# MasterRelayModule.net
KiCad netlist of a schematic drawn in Altium Designer
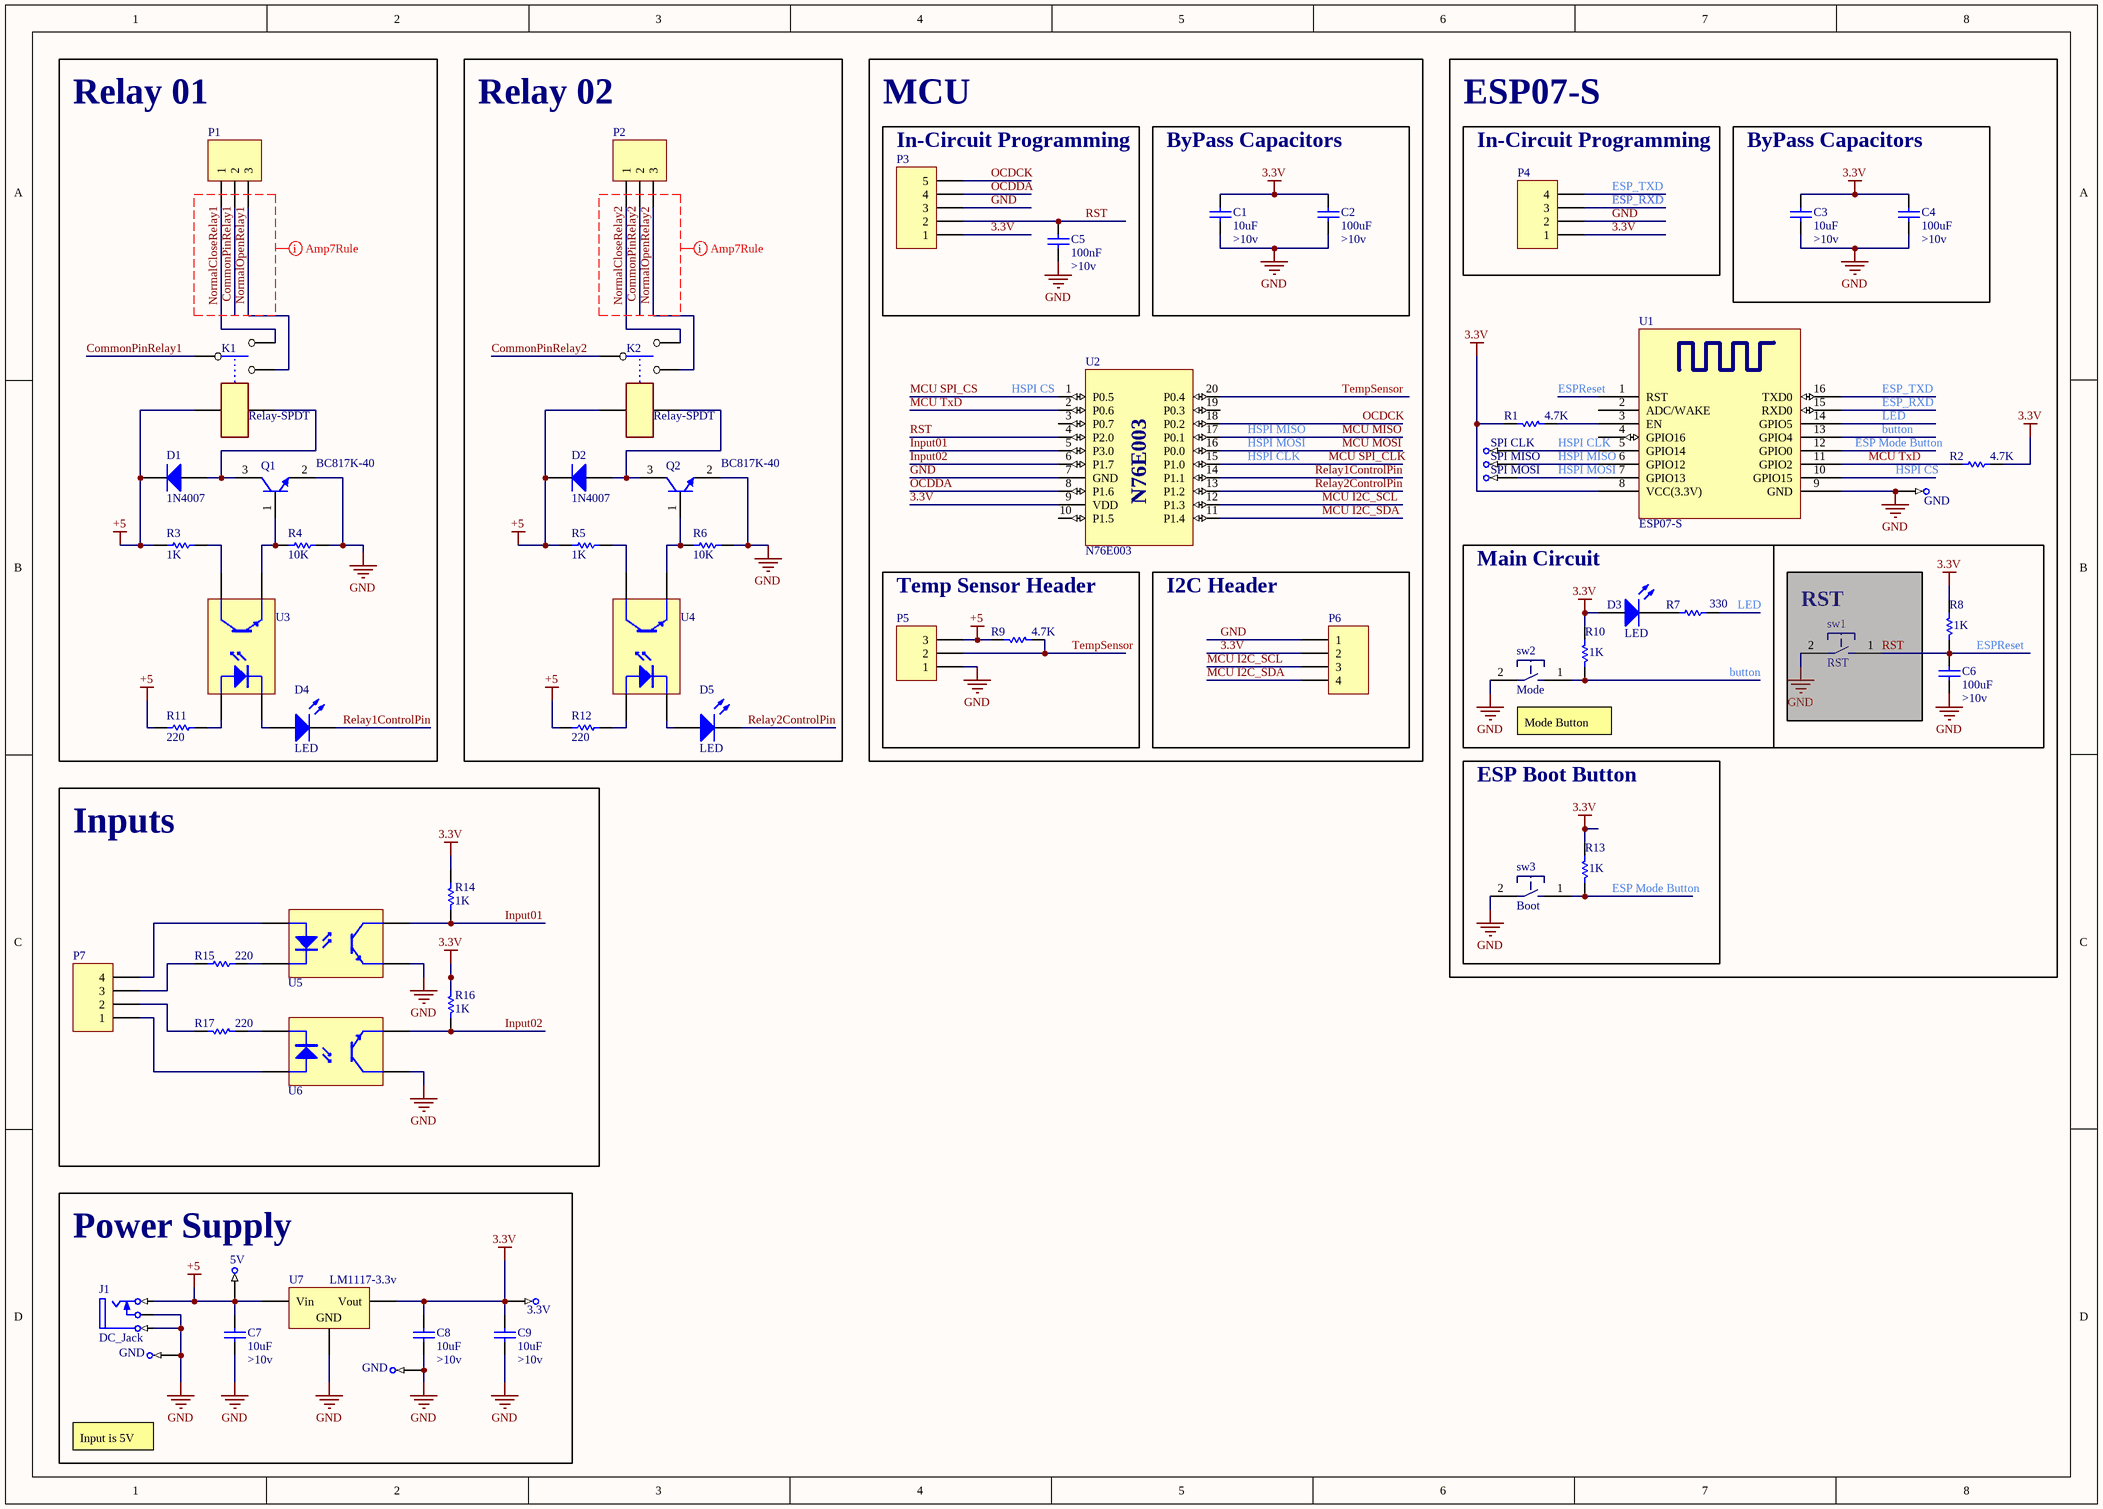
[diagram p0: MasterRelayModule.SchDoc]

(export (version "E")
  (design (tool "Eeschema 10.0.6"))
  (components
    (comp (ref "C1")
      (value "10uF")
      (footprint "MY_1210")
      (description "None polar capacitor")
      (fields (field (name "ASID PART NUMBER") "C-AS") (field (name "VOLTE") ">10v"))
      (libsource (lib "Mylib+Rev+4") (part "Cap ceramic"))
    )
    (comp (ref "C2")
      (value "100uF")
      (footprint "MY_1210")
      (description "None polar capacitor")
      (fields (field (name "ASID PART NUMBER") "C-AS") (field (name "VOLTE") ">10v"))
      (libsource (lib "Mylib+Rev+4") (part "Cap ceramic"))
    )
    (comp (ref "C3")
      (value "10uF")
      (footprint "MY_1210")
      (description "None polar capacitor")
      (fields (field (name "ASID PART NUMBER") "C-AS") (field (name "VOLTE") ">10v"))
      (libsource (lib "Mylib+Rev+4") (part "Cap ceramic"))
    )
    (comp (ref "C4")
      (value "100uF")
      (footprint "MY_1210")
      (description "None polar capacitor")
      (fields (field (name "ASID PART NUMBER") "C-AS") (field (name "VOLTE") ">10v"))
      (libsource (lib "Mylib+Rev+4") (part "Cap ceramic"))
    )
    (comp (ref "C5")
      (value "100nF")
      (footprint "MY_1210")
      (description "None polar capacitor")
      (fields (field (name "ASID PART NUMBER") "C-AS") (field (name "VOLTE") ">10v"))
      (libsource (lib "Mylib+Rev+4") (part "Cap ceramic"))
    )
    (comp (ref "C6")
      (value "100uF")
      (footprint "MY_1210")
      (description "None polar capacitor")
      (fields (field (name "ASID PART NUMBER") "C-AS") (field (name "VOLTE") ">10v"))
      (libsource (lib "Mylib+Rev+4") (part "Cap ceramic"))
    )
    (comp (ref "C7")
      (value "10uF")
      (footprint "MY_1210")
      (description "None polar capacitor")
      (fields (field (name "ASID PART NUMBER") "C-AS") (field (name "VOLTE") ">10v"))
      (libsource (lib "Mylib+Rev+4") (part "Cap ceramic"))
    )
    (comp (ref "C8")
      (value "10uF")
      (footprint "MY_1210")
      (description "None polar capacitor")
      (fields (field (name "ASID PART NUMBER") "C-AS") (field (name "VOLTE") ">10v"))
      (libsource (lib "Mylib+Rev+4") (part "Cap ceramic"))
    )
    (comp (ref "C9")
      (value "10uF")
      (footprint "MY_1210")
      (description "None polar capacitor")
      (fields (field (name "ASID PART NUMBER") "C-AS") (field (name "VOLTE") ">10v"))
      (libsource (lib "Mylib+Rev+4") (part "Cap ceramic"))
    )
    (comp (ref "D1")
      (value "1N4007")
      (footprint "MY_SMA")
      (description "1 Amp Diode")
      (fields (field (name "ASID PART NUMBER") "1n4007-AS"))
      (libsource (lib "Mylib+Rev+4") (part "1N4007"))
    )
    (comp (ref "D2")
      (value "1N4007")
      (footprint "MY_SMA")
      (description "1 Amp Diode")
      (fields (field (name "ASID PART NUMBER") "1n4007-AS"))
      (libsource (lib "Mylib+Rev+4") (part "1N4007"))
    )
    (comp (ref "D3")
      (value "LED")
      (footprint "MY_LED_0805")
      (description "Typical INFRARED GaAs LED")
      (fields (field (name "ASID PART NUMBER") "LED-AS"))
      (libsource (lib "Mylib+Rev+4") (part "LED"))
    )
    (comp (ref "D4")
      (value "LED")
      (footprint "MY_LED_0805")
      (description "Typical INFRARED GaAs LED")
      (fields (field (name "ASID PART NUMBER") "LED-AS"))
      (libsource (lib "Mylib+Rev+4") (part "LED"))
    )
    (comp (ref "D5")
      (value "LED")
      (footprint "MY_LED_0805")
      (description "Typical INFRARED GaAs LED")
      (fields (field (name "ASID PART NUMBER") "LED-AS"))
      (libsource (lib "Mylib+Rev+4") (part "LED"))
    )
    (comp (ref "J1")
      (value "DC_Jack")
      (footprint "My_DC_Jack")
      (fields (field (name "ASID PART NUMBER") "DC_Jack-AS"))
      (libsource (lib "Mylib+Rev+4") (part "DC_Jack"))
    )
    (comp (ref "K1")
      (value "Relay-SPDT")
      (footprint "My_rel")
      (description "Standard single contact relay")
      (fields (field (name "ASID PART NUMBER") "Relay-SPDT-AS"))
      (libsource (lib "Mylib+Rev+4") (part "Relay-SPDT"))
    )
    (comp (ref "K2")
      (value "Relay-SPDT")
      (footprint "My_rel")
      (description "Standard single contact relay")
      (fields (field (name "ASID PART NUMBER") "Relay-SPDT-AS"))
      (libsource (lib "Mylib+Rev+4") (part "Relay-SPDT"))
    )
    (comp (ref "P1")
      (value "Header 3")
      (footprint "MY_MSTBA3")
      (description "Header, 3-Pin")
      (fields (field (name "ASID PART NUMBER") "Header 3-AS"))
      (libsource (lib "") (part "Header 3_1"))
    )
    (comp (ref "P2")
      (value "Header 3")
      (footprint "MY_MSTBA3")
      (description "Header, 3-Pin")
      (fields (field (name "ASID PART NUMBER") "Header 3-AS"))
      (libsource (lib "") (part "Header 3_1"))
    )
    (comp (ref "P3")
      (value "Header 5")
      (footprint "My_1X05")
      (description "Header, 5-Pin")
      (fields (field (name "ASID PART NUMBER") "Header 5-AS"))
      (libsource (lib "Mylib+Rev+4") (part "Header 5"))
    )
    (comp (ref "P4")
      (value "Header 4")
      (footprint "My_1X04")
      (description "Header, 4-Pin")
      (fields (field (name "ASID PART NUMBER") "Header 4-AS"))
      (libsource (lib "") (part "Header 4_1"))
    )
    (comp (ref "P5")
      (value "Header 3")
      (footprint "My_1X03")
      (description "Header, 3-Pin")
      (fields (field (name "ASID PART NUMBER") "Header 3-AS"))
      (libsource (lib "Mylib+Rev+4") (part "Header 3"))
    )
    (comp (ref "P6")
      (value "Header 4")
      (footprint "MY_FE04W")
      (description "Header, 4-Pin")
      (fields (field (name "ASID PART NUMBER") "Header 4-AS"))
      (libsource (lib "Mylib+Rev+4") (part "Header 4"))
    )
    (comp (ref "P7")
      (value "Header 4")
      (footprint "MY_MSTBA4")
      (description "Header, 4-Pin")
      (fields (field (name "ASID PART NUMBER") "Header 4-AS"))
      (libsource (lib "") (part "Header 4_1"))
    )
    (comp (ref "Q1")
      (value "BC817K-40")
      (footprint "INF-SOT23_N")
      (description "NPN Silicon AF Transistor, 45 V VCEO, 500 mA IC, SOT23, Reel, Green")
      (fields (field (name "MANUFACTURER") "Infineon"))
      (libsource (lib "Infineon_Transistor_&_Diode") (part "BC817K-40"))
    )
    (comp (ref "Q2")
      (value "BC817K-40")
      (footprint "INF-SOT23_N")
      (description "NPN Silicon AF Transistor, 45 V VCEO, 500 mA IC, SOT23, Reel, Green")
      (fields (field (name "MANUFACTURER") "Infineon"))
      (libsource (lib "Infineon_Transistor_&_Diode") (part "BC817K-40"))
    )
    (comp (ref "R1")
      (value "4.7K")
      (footprint "MY_0805")
      (description "Standard resistor")
      (fields (field (name "ASID PART NUMBER") "Res-AS"))
      (libsource (lib "Mylib+Rev+4") (part "Res"))
    )
    (comp (ref "R2")
      (value "4.7K")
      (footprint "MY_0805")
      (description "Standard resistor")
      (fields (field (name "ASID PART NUMBER") "Res-AS"))
      (libsource (lib "Mylib+Rev+4") (part "Res"))
    )
    (comp (ref "R3")
      (value "1K")
      (footprint "MY_0805")
      (description "Standard resistor")
      (fields (field (name "ASID PART NUMBER") "Res-AS"))
      (libsource (lib "Mylib+Rev+4") (part "Res"))
    )
    (comp (ref "R4")
      (value "10K")
      (footprint "MY_0805")
      (description "Standard resistor")
      (fields (field (name "ASID PART NUMBER") "Res-AS"))
      (libsource (lib "Mylib+Rev+4") (part "Res"))
    )
    (comp (ref "R5")
      (value "1K")
      (footprint "MY_0805")
      (description "Standard resistor")
      (fields (field (name "ASID PART NUMBER") "Res-AS"))
      (libsource (lib "Mylib+Rev+4") (part "Res"))
    )
    (comp (ref "R6")
      (value "10K")
      (footprint "MY_0805")
      (description "Standard resistor")
      (fields (field (name "ASID PART NUMBER") "Res-AS"))
      (libsource (lib "Mylib+Rev+4") (part "Res"))
    )
    (comp (ref "R7")
      (value "330")
      (footprint "MY_0805")
      (description "Standard resistor")
      (fields (field (name "ASID PART NUMBER") "Res-AS"))
      (libsource (lib "Mylib+Rev+4") (part "Res"))
    )
    (comp (ref "R8")
      (value "1K")
      (footprint "MY_0805")
      (description "Standard resistor")
      (fields (field (name "ASID PART NUMBER") "Res-AS"))
      (libsource (lib "Mylib+Rev+4") (part "Res"))
    )
    (comp (ref "R9")
      (value "4.7K")
      (footprint "MY_0805")
      (description "Standard resistor")
      (fields (field (name "ASID PART NUMBER") "Res-AS"))
      (libsource (lib "Mylib+Rev+4") (part "Res"))
    )
    (comp (ref "R10")
      (value "1K")
      (footprint "MY_0805")
      (description "Standard resistor")
      (fields (field (name "ASID PART NUMBER") "Res-AS"))
      (libsource (lib "Mylib+Rev+4") (part "Res"))
    )
    (comp (ref "R11")
      (value "220")
      (footprint "MY_0805")
      (description "Standard resistor")
      (fields (field (name "ASID PART NUMBER") "Res-AS"))
      (libsource (lib "Mylib+Rev+4") (part "Res"))
    )
    (comp (ref "R12")
      (value "220")
      (footprint "MY_0805")
      (description "Standard resistor")
      (fields (field (name "ASID PART NUMBER") "Res-AS"))
      (libsource (lib "Mylib+Rev+4") (part "Res"))
    )
    (comp (ref "R13")
      (value "1K")
      (footprint "MY_0805")
      (description "Standard resistor")
      (fields (field (name "ASID PART NUMBER") "Res-AS"))
      (libsource (lib "Mylib+Rev+4") (part "Res"))
    )
    (comp (ref "R14")
      (value "1K")
      (footprint "MY_0805")
      (description "Standard resistor")
      (fields (field (name "ASID PART NUMBER") "Res-AS"))
      (libsource (lib "Mylib+Rev+4") (part "Res"))
    )
    (comp (ref "R15")
      (value "220")
      (footprint "MY_0805")
      (description "Standard resistor")
      (fields (field (name "ASID PART NUMBER") "Res-AS"))
      (libsource (lib "Mylib+Rev+4") (part "Res"))
    )
    (comp (ref "R16")
      (value "1K")
      (footprint "MY_0805")
      (description "Standard resistor")
      (fields (field (name "ASID PART NUMBER") "Res-AS"))
      (libsource (lib "Mylib+Rev+4") (part "Res"))
    )
    (comp (ref "R17")
      (value "220")
      (footprint "MY_0805")
      (description "Standard resistor")
      (fields (field (name "ASID PART NUMBER") "Res-AS"))
      (libsource (lib "Mylib+Rev+4") (part "Res"))
    )
    (comp (ref "sw1")
      (value "RST")
      (footprint "MY_TACTILE-SMD")
      (description "small tac switch")
      (fields (field (name "ASID PART NUMBER") "Tac switch-AS"))
      (libsource (lib "Mylib+Rev+4") (part "Tac switch"))
    )
    (comp (ref "sw2")
      (value "Mode")
      (footprint "MY_TACTILE-SMD")
      (description "small tac switch")
      (fields (field (name "ASID PART NUMBER") "Tac switch-AS"))
      (libsource (lib "Mylib+Rev+4") (part "Tac switch"))
    )
    (comp (ref "sw3")
      (value "Boot")
      (footprint "MY_TACTILE-SMD")
      (description "small tac switch")
      (fields (field (name "ASID PART NUMBER") "Tac switch-AS"))
      (libsource (lib "Mylib+Rev+4") (part "Tac switch"))
    )
    (comp (ref "TP1")
      (value "SPI CLK")
      (footprint "MY_Testpad1")
      (description "Test point")
      (fields (field (name "ASID PART NUMBER") "Test Point-AS"))
      (libsource (lib "Mylib+Rev+4") (part "Test Point"))
    )
    (comp (ref "TP2")
      (value "SPI MISO")
      (footprint "MY_Testpad1")
      (description "Test point")
      (fields (field (name "ASID PART NUMBER") "Test Point-AS"))
      (libsource (lib "Mylib+Rev+4") (part "Test Point"))
    )
    (comp (ref "TP3")
      (value "SPI MOSI")
      (footprint "MY_Testpad1")
      (description "Test point")
      (fields (field (name "ASID PART NUMBER") "Test Point-AS"))
      (libsource (lib "Mylib+Rev+4") (part "Test Point"))
    )
    (comp (ref "TP4")
      (value "5V")
      (footprint "MY_Testpad1")
      (description "Test point")
      (fields (field (name "ASID PART NUMBER") "Test Point-AS"))
      (libsource (lib "Mylib+Rev+4") (part "Test Point"))
    )
    (comp (ref "TP5")
      (value "3.3V")
      (footprint "MY_Testpad1")
      (description "Test point")
      (fields (field (name "ASID PART NUMBER") "Test Point-AS"))
      (libsource (lib "Mylib+Rev+4") (part "Test Point"))
    )
    (comp (ref "TP6")
      (value "GND")
      (footprint "MY_Testpad1")
      (description "Test point")
      (fields (field (name "ASID PART NUMBER") "Test Point-AS"))
      (libsource (lib "Mylib+Rev+4") (part "Test Point"))
    )
    (comp (ref "TP7")
      (value "GND")
      (footprint "MY_Testpad1")
      (description "Test point")
      (fields (field (name "ASID PART NUMBER") "Test Point-AS"))
      (libsource (lib "Mylib+Rev+4") (part "Test Point"))
    )
    (comp (ref "TP8")
      (value "GND")
      (footprint "MY_Testpad1")
      (description "Test point")
      (fields (field (name "ASID PART NUMBER") "Test Point-AS"))
      (libsource (lib "Mylib+Rev+4") (part "Test Point"))
    )
    (comp (ref "U1") (value "ESP07-S") (footprint "ESP07-S") (libsource (lib "myLib") (part "ESP07-S")))
    (comp (ref "U2") (value "N76E003") (footprint "SOP_20") (libsource (lib "myLib") (part "N76E003")))
    (comp (ref "U3")
      (value "Optoisolator")
      (footprint "MY_OPTO_SMD4-7")
      (fields (field (name "ASID PART NUMBER") "Optoisolator-AS"))
      (libsource (lib "Mylib+Rev+4") (part "Optoisolator"))
    )
    (comp (ref "U4")
      (value "Optoisolator")
      (footprint "MY_OPTO_SMD4-7")
      (fields (field (name "ASID PART NUMBER") "Optoisolator-AS"))
      (libsource (lib "Mylib+Rev+4") (part "Optoisolator"))
    )
    (comp (ref "U5")
      (value "Optoisolator")
      (footprint "MY_OPTO_SMD4-7")
      (fields (field (name "ASID PART NUMBER") "Optoisolator-AS"))
      (libsource (lib "") (part "Optoisolator_1"))
    )
    (comp (ref "U6")
      (value "Optoisolator")
      (footprint "MY_OPTO_SMD4-7")
      (fields (field (name "ASID PART NUMBER") "Optoisolator-AS"))
      (libsource (lib "Mylib+Rev+4") (part "Optoisolator"))
    )
    (comp (ref "U7")
      (value "LM1117-3.3v")
      (footprint "MY_SOT223")
      (description "Low Drop Voltage Reg")
      (fields (field (name "ASID PART NUMBER") "LM1117-AS"))
      (libsource (lib "Mylib+Rev+4") (part "LM1117"))
    )
  )
  (nets
    (net (code "1") (name "+5") (class "Default")
      (node (ref "C7") (pin "2") (pinfunction "2_2") (pintype "passive"))
      (node (ref "D1") (pin "K") (pinfunction "K_K") (pintype "passive"))
      (node (ref "D2") (pin "K") (pinfunction "K_K") (pintype "passive"))
      (node (ref "J1") (pin "1") (pinfunction "T_1") (pintype "input"))
      (node (ref "K1") (pin "4") (pinfunction "4_4") (pintype "passive"))
      (node (ref "K2") (pin "4") (pinfunction "4_4") (pintype "passive"))
      (node (ref "P5") (pin "3") (pinfunction "3_3") (pintype "passive"))
      (node (ref "R11") (pin "2") (pinfunction "2_2") (pintype "passive"))
      (node (ref "R12") (pin "2") (pinfunction "2_2") (pintype "passive"))
      (node (ref "R3") (pin "2") (pinfunction "2_2") (pintype "passive"))
      (node (ref "R5") (pin "2") (pinfunction "2_2") (pintype "passive"))
      (node (ref "R9") (pin "1") (pinfunction "1_1") (pintype "passive"))
      (node (ref "TP4") (pin "1") (pinfunction "1_1") (pintype "input"))
      (node (ref "U7") (pin "3") (pinfunction "Vin_3") (pintype "passive"))
    )
    (net (code "2") (name "/CommonPinRelay1") (class "Default")
      (node (ref "K1") (pin "1") (pinfunction "1_1") (pintype "passive"))
      (node (ref "P1") (pin "2") (pinfunction "2_2") (pintype "passive"))
    )
    (net (code "3") (name "/CommonPinRelay2") (class "Default")
      (node (ref "K2") (pin "1") (pinfunction "1_1") (pintype "passive"))
      (node (ref "P2") (pin "2") (pinfunction "2_2") (pintype "passive"))
    )
    (net (code "4") (name "/ESP Mode Button") (class "Default")
      (node (ref "R13") (pin "2") (pinfunction "2_2") (pintype "passive"))
      (node (ref "U1") (pin "12") (pinfunction "GPIO0_12") (pintype "passive"))
      (node (ref "sw3") (pin "1") (pinfunction "1_1") (pintype "passive"))
    )
    (net (code "5") (name "/ESPReset") (class "Default")
      (node (ref "C5") (pin "2") (pinfunction "2_2") (pintype "passive"))
      (node (ref "C6") (pin "2") (pinfunction "2_2") (pintype "passive"))
      (node (ref "P3") (pin "2") (pinfunction "2_2") (pintype "passive"))
      (node (ref "R8") (pin "2") (pinfunction "2_2") (pintype "passive"))
      (node (ref "U1") (pin "1") (pinfunction "RST_1") (pintype "passive"))
      (node (ref "U2") (pin "4") (pinfunction "P2.0_4") (pintype "bidirectional"))
      (node (ref "sw1") (pin "1") (pinfunction "1_1") (pintype "passive"))
    )
    (net (code "6") (name "/ESP_RXD") (class "Default")
      (node (ref "P4") (pin "3") (pinfunction "3_3") (pintype "passive"))
      (node (ref "U1") (pin "15") (pinfunction "RXD0_15") (pintype "bidirectional"))
    )
    (net (code "7") (name "/ESP_TXD") (class "Default")
      (node (ref "P4") (pin "4") (pinfunction "4_4") (pintype "passive"))
      (node (ref "U1") (pin "16") (pinfunction "TXD0_16") (pintype "bidirectional"))
    )
    (net (code "8") (name "/HSPI CLK") (class "Default")
      (node (ref "TP1") (pin "1") (pinfunction "1_1") (pintype "input"))
      (node (ref "U1") (pin "5") (pinfunction "GPIO14_5") (pintype "passive"))
      (node (ref "U2") (pin "15") (pinfunction "P1.0_15") (pintype "bidirectional"))
    )
    (net (code "9") (name "/HSPI CS") (class "Default")
      (node (ref "U1") (pin "10") (pinfunction "GPIO15_10") (pintype "passive"))
      (node (ref "U2") (pin "1") (pinfunction "P0.5_1") (pintype "bidirectional"))
    )
    (net (code "10") (name "/HSPI MISO") (class "Default")
      (node (ref "TP2") (pin "1") (pinfunction "1_1") (pintype "input"))
      (node (ref "U1") (pin "6") (pinfunction "GPIO12_6") (pintype "passive"))
      (node (ref "U2") (pin "17") (pinfunction "P0.1_17") (pintype "bidirectional"))
    )
    (net (code "11") (name "/HSPI MOSI") (class "Default")
      (node (ref "TP3") (pin "1") (pinfunction "1_1") (pintype "input"))
      (node (ref "U1") (pin "7") (pinfunction "GPIO13_7") (pintype "passive"))
      (node (ref "U2") (pin "16") (pinfunction "P0.0_16") (pintype "bidirectional"))
    )
    (net (code "12") (name "/Input01") (class "Default")
      (node (ref "R14") (pin "2") (pinfunction "2_2") (pintype "passive"))
      (node (ref "U2") (pin "5") (pinfunction "P3.0_5") (pintype "bidirectional"))
      (node (ref "U5") (pin "4") (pinfunction "C_4") (pintype "passive"))
    )
    (net (code "13") (name "/Input02") (class "Default")
      (node (ref "R16") (pin "2") (pinfunction "2_2") (pintype "passive"))
      (node (ref "U2") (pin "6") (pinfunction "P1.7_6") (pintype "bidirectional"))
      (node (ref "U6") (pin "3") (pinfunction "E_3") (pintype "passive"))
    )
    (net (code "14") (name "/LED") (class "Default")
      (node (ref "R7") (pin "2") (pinfunction "2_2") (pintype "passive"))
      (node (ref "U1") (pin "14") (pinfunction "GPIO5_14") (pintype "passive"))
    )
    (net (code "15") (name "/MCU I2C_SCL") (class "Default")
      (node (ref "P6") (pin "3") (pinfunction "3_3") (pintype "passive"))
      (node (ref "U2") (pin "12") (pinfunction "P1.3_12") (pintype "bidirectional"))
    )
    (net (code "16") (name "/MCU I2C_SDA") (class "Default")
      (node (ref "P6") (pin "4") (pinfunction "4_4") (pintype "passive"))
      (node (ref "U2") (pin "11") (pinfunction "P1.4_11") (pintype "bidirectional"))
    )
    (net (code "17") (name "/MCU TxD") (class "Default")
      (node (ref "R2") (pin "2") (pinfunction "2_2") (pintype "passive"))
      (node (ref "U1") (pin "11") (pinfunction "GPIO2_11") (pintype "passive"))
      (node (ref "U2") (pin "2") (pinfunction "P0.6_2") (pintype "bidirectional"))
    )
    (net (code "18") (name "/NormalCloseRelay1") (class "Default")
      (node (ref "K1") (pin "2") (pinfunction "2_2") (pintype "passive"))
      (node (ref "P1") (pin "1") (pinfunction "1_1") (pintype "passive"))
    )
    (net (code "19") (name "/NormalCloseRelay2") (class "Default")
      (node (ref "K2") (pin "2") (pinfunction "2_2") (pintype "passive"))
      (node (ref "P2") (pin "1") (pinfunction "1_1") (pintype "passive"))
    )
    (net (code "20") (name "/NormalOpenRelay1") (class "Default")
      (node (ref "K1") (pin "3") (pinfunction "3_3") (pintype "passive"))
      (node (ref "P1") (pin "3") (pinfunction "3_3") (pintype "passive"))
    )
    (net (code "21") (name "/NormalOpenRelay2") (class "Default")
      (node (ref "K2") (pin "3") (pinfunction "3_3") (pintype "passive"))
      (node (ref "P2") (pin "3") (pinfunction "3_3") (pintype "passive"))
    )
    (net (code "22") (name "/OCDCK") (class "Default")
      (node (ref "P3") (pin "5") (pinfunction "5_5") (pintype "passive"))
      (node (ref "U2") (pin "18") (pinfunction "P0.2_18") (pintype "bidirectional"))
    )
    (net (code "23") (name "/OCDDA") (class "Default")
      (node (ref "P3") (pin "4") (pinfunction "4_4") (pintype "passive"))
      (node (ref "U2") (pin "8") (pinfunction "P1.6_8") (pintype "bidirectional"))
    )
    (net (code "24") (name "/Relay1ControlPin") (class "Default")
      (node (ref "D4") (pin "K") (pinfunction "K_K") (pintype "passive"))
      (node (ref "U2") (pin "14") (pinfunction "P1.1_14") (pintype "bidirectional"))
    )
    (net (code "25") (name "/Relay2ControlPin") (class "Default")
      (node (ref "D5") (pin "K") (pinfunction "K_K") (pintype "passive"))
      (node (ref "U2") (pin "13") (pinfunction "P1.2_13") (pintype "bidirectional"))
    )
    (net (code "26") (name "/TempSensor") (class "Default")
      (node (ref "P5") (pin "2") (pinfunction "2_2") (pintype "passive"))
      (node (ref "R9") (pin "2") (pinfunction "2_2") (pintype "passive"))
      (node (ref "U2") (pin "20") (pinfunction "P0.4_20") (pintype "bidirectional"))
    )
    (net (code "27") (name "/button") (class "Default")
      (node (ref "R10") (pin "2") (pinfunction "2_2") (pintype "passive"))
      (node (ref "U1") (pin "13") (pinfunction "GPIO4_13") (pintype "passive"))
      (node (ref "sw2") (pin "1") (pinfunction "1_1") (pintype "passive"))
    )
    (net (code "28") (name "3.3V") (class "Default")
      (node (ref "C1") (pin "2") (pinfunction "2_2") (pintype "passive"))
      (node (ref "C2") (pin "2") (pinfunction "2_2") (pintype "passive"))
      (node (ref "C3") (pin "2") (pinfunction "2_2") (pintype "passive"))
      (node (ref "C4") (pin "2") (pinfunction "2_2") (pintype "passive"))
      (node (ref "C8") (pin "2") (pinfunction "2_2") (pintype "passive"))
      (node (ref "C9") (pin "2") (pinfunction "2_2") (pintype "passive"))
      (node (ref "D3") (pin "A") (pinfunction "A_A") (pintype "passive"))
      (node (ref "P3") (pin "1") (pinfunction "1_1") (pintype "passive"))
      (node (ref "P4") (pin "1") (pinfunction "1_1") (pintype "passive"))
      (node (ref "P6") (pin "2") (pinfunction "2_2") (pintype "passive"))
      (node (ref "R1") (pin "1") (pinfunction "1_1") (pintype "passive"))
      (node (ref "R10") (pin "1") (pinfunction "1_1") (pintype "passive"))
      (node (ref "R13") (pin "1") (pinfunction "1_1") (pintype "passive"))
      (node (ref "R14") (pin "1") (pinfunction "1_1") (pintype "passive"))
      (node (ref "R16") (pin "1") (pinfunction "1_1") (pintype "passive"))
      (node (ref "R2") (pin "1") (pinfunction "1_1") (pintype "passive"))
      (node (ref "R8") (pin "1") (pinfunction "1_1") (pintype "passive"))
      (node (ref "TP5") (pin "1") (pinfunction "1_1") (pintype "input"))
      (node (ref "U1") (pin "8") (pinfunction "VCC(3.3V)_8") (pintype "passive"))
      (node (ref "U2") (pin "9") (pinfunction "VDD_9") (pintype "power_in"))
      (node (ref "U7") (pin "2") (pinfunction "Vout_2") (pintype "passive"))
    )
    (net (code "29") (name "GND") (class "Default")
      (node (ref "C1") (pin "1") (pinfunction "1_1") (pintype "passive"))
      (node (ref "C2") (pin "1") (pinfunction "1_1") (pintype "passive"))
      (node (ref "C3") (pin "1") (pinfunction "1_1") (pintype "passive"))
      (node (ref "C4") (pin "1") (pinfunction "1_1") (pintype "passive"))
      (node (ref "C5") (pin "1") (pinfunction "1_1") (pintype "passive"))
      (node (ref "C6") (pin "1") (pinfunction "1_1") (pintype "passive"))
      (node (ref "C7") (pin "1") (pinfunction "1_1") (pintype "passive"))
      (node (ref "C8") (pin "1") (pinfunction "1_1") (pintype "passive"))
      (node (ref "C9") (pin "1") (pinfunction "1_1") (pintype "passive"))
      (node (ref "J1") (pin "2") (pinfunction "TN_2") (pintype "passive"))
      (node (ref "J1") (pin "3") (pinfunction "S_3") (pintype "input"))
      (node (ref "P3") (pin "3") (pinfunction "3_3") (pintype "passive"))
      (node (ref "P4") (pin "2") (pinfunction "2_2") (pintype "passive"))
      (node (ref "P5") (pin "1") (pinfunction "1_1") (pintype "passive"))
      (node (ref "P6") (pin "1") (pinfunction "1_1") (pintype "passive"))
      (node (ref "Q1") (pin "2") (pinfunction "E_2") (pintype "passive"))
      (node (ref "Q2") (pin "2") (pinfunction "E_2") (pintype "passive"))
      (node (ref "R4") (pin "1") (pinfunction "1_1") (pintype "passive"))
      (node (ref "R6") (pin "1") (pinfunction "1_1") (pintype "passive"))
      (node (ref "TP6") (pin "1") (pinfunction "1_1") (pintype "input"))
      (node (ref "TP7") (pin "1") (pinfunction "1_1") (pintype "input"))
      (node (ref "TP8") (pin "1") (pinfunction "1_1") (pintype "input"))
      (node (ref "U1") (pin "9") (pinfunction "GND_9") (pintype "passive"))
      (node (ref "U2") (pin "7") (pinfunction "GND_7") (pintype "power_in"))
      (node (ref "U5") (pin "3") (pinfunction "E_3") (pintype "passive"))
      (node (ref "U6") (pin "4") (pinfunction "C_4") (pintype "passive"))
      (node (ref "U7") (pin "1") (pinfunction "GND_1") (pintype "passive"))
      (node (ref "sw1") (pin "2") (pinfunction "2_2") (pintype "passive"))
      (node (ref "sw2") (pin "2") (pinfunction "2_2") (pintype "passive"))
      (node (ref "sw3") (pin "2") (pinfunction "2_2") (pintype "passive"))
    )
    (net (code "30") (name "Net-(D3-PadK)") (class "Default")
      (node (ref "D3") (pin "K") (pinfunction "K_K") (pintype "passive"))
      (node (ref "R7") (pin "1") (pinfunction "1_1") (pintype "passive"))
    )
    (net (code "31") (name "Net-(P7-Pad2)") (class "Default")
      (node (ref "P7") (pin "2") (pinfunction "2_2") (pintype "passive"))
      (node (ref "R17") (pin "2") (pinfunction "2_2") (pintype "passive"))
    )
    (net (code "32") (name "Net-(P7-Pad3)") (class "Default")
      (node (ref "P7") (pin "3") (pinfunction "3_3") (pintype "passive"))
      (node (ref "R15") (pin "2") (pinfunction "2_2") (pintype "passive"))
    )
    (net (code "33") (name "Net-(Q1-B)") (class "Default")
      (node (ref "Q1") (pin "1") (pinfunction "B_1") (pintype "passive"))
      (node (ref "R4") (pin "2") (pinfunction "2_2") (pintype "passive"))
      (node (ref "U3") (pin "3") (pinfunction "E_3") (pintype "passive"))
    )
    (net (code "34") (name "Net-(Q1-C)") (class "Default")
      (node (ref "D1") (pin "A") (pinfunction "A_A") (pintype "passive"))
      (node (ref "K1") (pin "5") (pinfunction "5_5") (pintype "passive"))
      (node (ref "Q1") (pin "3") (pinfunction "C_3") (pintype "passive"))
    )
    (net (code "35") (name "Net-(Q2-B)") (class "Default")
      (node (ref "Q2") (pin "1") (pinfunction "B_1") (pintype "passive"))
      (node (ref "R6") (pin "2") (pinfunction "2_2") (pintype "passive"))
      (node (ref "U4") (pin "3") (pinfunction "E_3") (pintype "passive"))
    )
    (net (code "36") (name "Net-(Q2-C)") (class "Default")
      (node (ref "D2") (pin "A") (pinfunction "A_A") (pintype "passive"))
      (node (ref "K2") (pin "5") (pinfunction "5_5") (pintype "passive"))
      (node (ref "Q2") (pin "3") (pinfunction "C_3") (pintype "passive"))
    )
    (net (code "37") (name "Net-(U1-EN)") (class "Default")
      (node (ref "R1") (pin "2") (pinfunction "2_2") (pintype "passive"))
      (node (ref "U1") (pin "3") (pinfunction "EN_3") (pintype "passive"))
    )
    (net (code "38") (name "Net-(U3-A)") (class "Default")
      (node (ref "R11") (pin "1") (pinfunction "1_1") (pintype "passive"))
      (node (ref "U3") (pin "1") (pinfunction "A_1") (pintype "passive"))
    )
    (net (code "39") (name "Net-(U3-C)") (class "Default")
      (node (ref "R3") (pin "1") (pinfunction "1_1") (pintype "passive"))
      (node (ref "U3") (pin "4") (pinfunction "C_4") (pintype "passive"))
    )
    (net (code "40") (name "Net-(U3-K)") (class "Default")
      (node (ref "D4") (pin "A") (pinfunction "A_A") (pintype "passive"))
      (node (ref "U3") (pin "2") (pinfunction "K_2") (pintype "passive"))
    )
    (net (code "41") (name "Net-(U4-A)") (class "Default")
      (node (ref "R12") (pin "1") (pinfunction "1_1") (pintype "passive"))
      (node (ref "U4") (pin "1") (pinfunction "A_1") (pintype "passive"))
    )
    (net (code "42") (name "Net-(U4-C)") (class "Default")
      (node (ref "R5") (pin "1") (pinfunction "1_1") (pintype "passive"))
      (node (ref "U4") (pin "4") (pinfunction "C_4") (pintype "passive"))
    )
    (net (code "43") (name "Net-(U4-K)") (class "Default")
      (node (ref "D5") (pin "A") (pinfunction "A_A") (pintype "passive"))
      (node (ref "U4") (pin "2") (pinfunction "K_2") (pintype "passive"))
    )
    (net (code "44") (name "Net-(U5-A)") (class "Default")
      (node (ref "P7") (pin "4") (pinfunction "4_4") (pintype "passive"))
      (node (ref "U5") (pin "1") (pinfunction "A_1") (pintype "passive"))
    )
    (net (code "45") (name "Net-(U5-K)") (class "Default")
      (node (ref "R15") (pin "1") (pinfunction "1_1") (pintype "passive"))
      (node (ref "U5") (pin "2") (pinfunction "K_2") (pintype "passive"))
    )
    (net (code "46") (name "Net-(U6-A)") (class "Default")
      (node (ref "P7") (pin "1") (pinfunction "1_1") (pintype "passive"))
      (node (ref "U6") (pin "1") (pinfunction "A_1") (pintype "passive"))
    )
    (net (code "47") (name "Net-(U6-K)") (class "Default")
      (node (ref "R17") (pin "1") (pinfunction "1_1") (pintype "passive"))
      (node (ref "U6") (pin "2") (pinfunction "K_2") (pintype "passive"))
    )
    (net (code "48") (name "unconnected-(U1-ADC{slash}WAKE-Pad2)") (class "Default")
      (node (ref "U1") (pin "2") (pinfunction "ADC/WAKE_2") (pintype "passive"))
    )
    (net (code "49") (name "unconnected-(U1-GPIO16-Pad4)") (class "Default")
      (node (ref "U1") (pin "4") (pinfunction "GPIO16_4") (pintype "bidirectional"))
    )
    (net (code "50") (name "unconnected-(U2-P0.3-Pad19)") (class "Default")
      (node (ref "U2") (pin "19") (pinfunction "P0.3_19") (pintype "bidirectional"))
    )
    (net (code "51") (name "unconnected-(U2-P0.7-Pad3)") (class "Default")
      (node (ref "U2") (pin "3") (pinfunction "P0.7_3") (pintype "bidirectional"))
    )
    (net (code "52") (name "unconnected-(U2-P1.5-Pad10)") (class "Default")
      (node (ref "U2") (pin "10") (pinfunction "P1.5_10") (pintype "bidirectional"))
    )
  )
)
